# aparture_v1.net
KiCad netlist of a schematic drawn in EAGLE
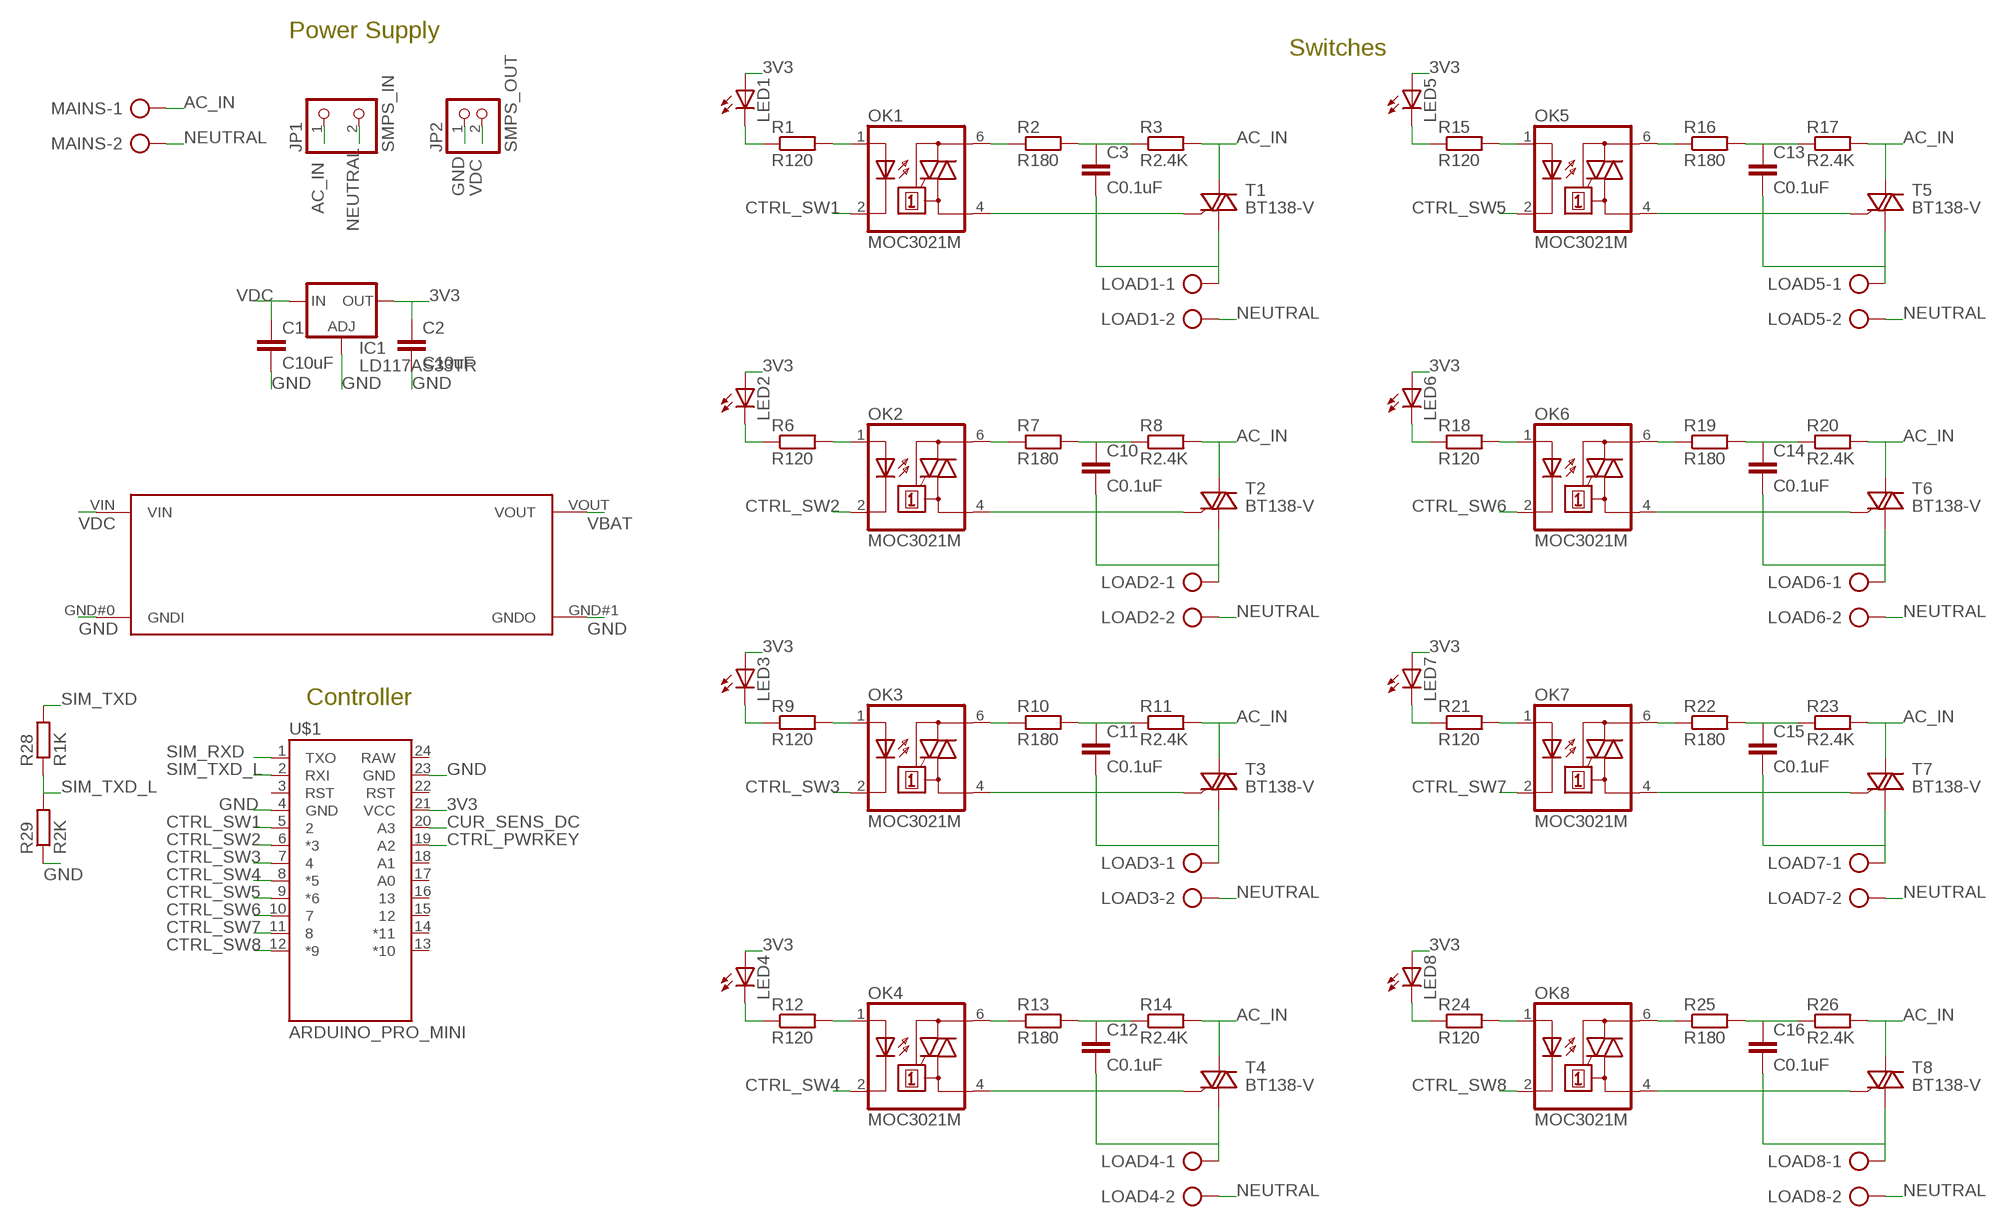
[diagram p0: schematic, sheet 1, part 1 of 2]
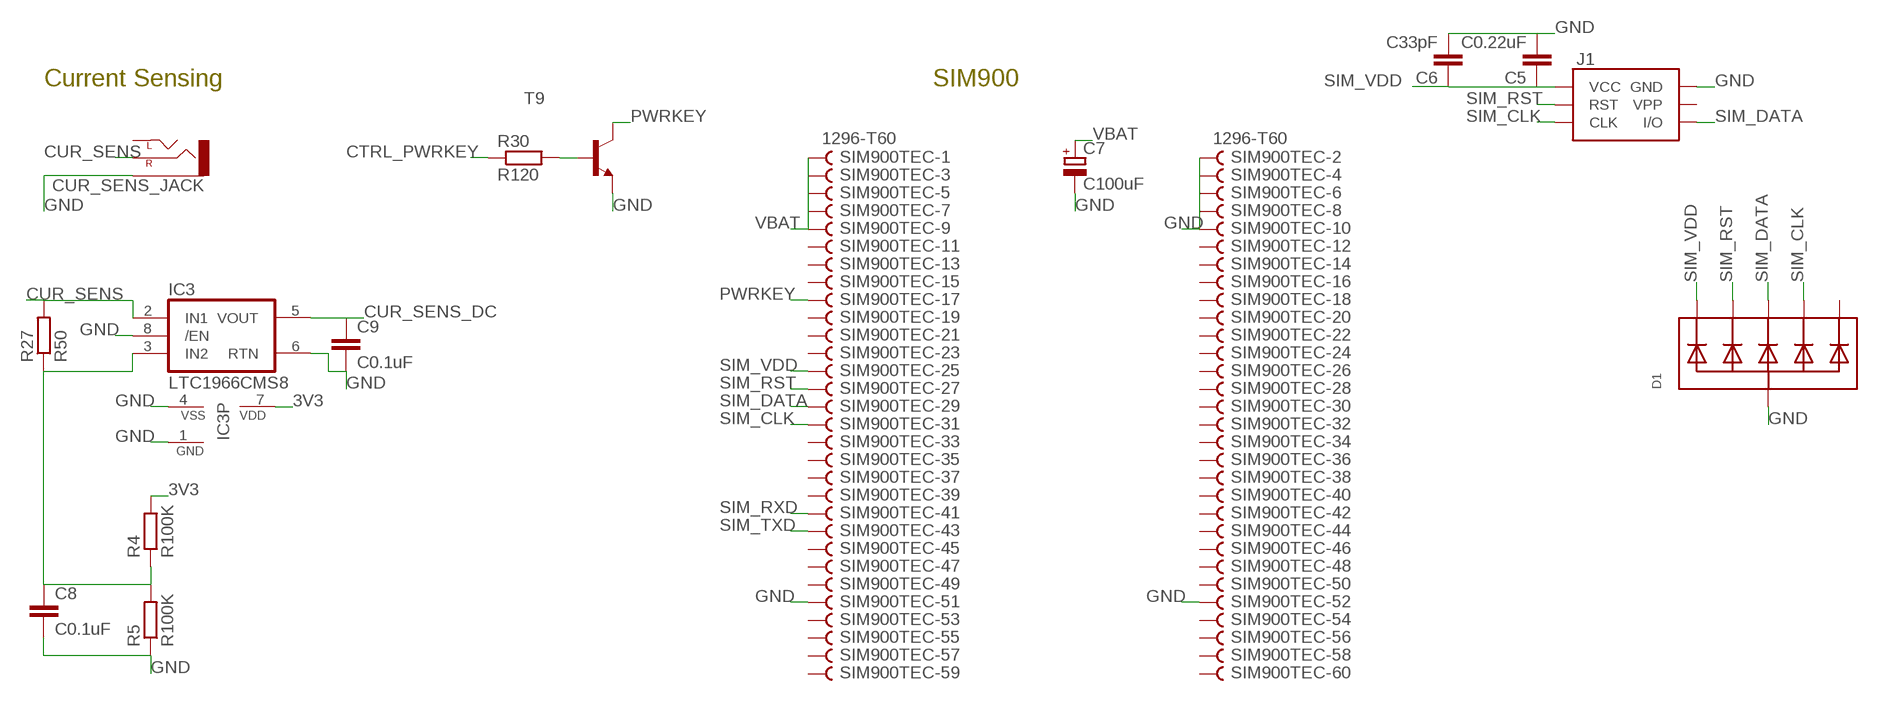
[diagram p1: schematic, sheet 1, part 2 of 2]

(export (version "E")
  (design (tool "Eeschema 10.0.6"))
  (components
    (comp (ref "C1")
      (value "C10uF")
      (footprint "eagle-import:C0805")
      (libsource (lib "eagle-import") (part "C-EUC0805"))
    )
    (comp (ref "C2")
      (value "C10uF")
      (footprint "eagle-import:C0805")
      (libsource (lib "eagle-import") (part "C-EUC0805"))
    )
    (comp (ref "C3")
      (value "C0.1uF")
      (footprint "eagle-import:C0805")
      (libsource (lib "eagle-import") (part "C-EUC0805"))
    )
    (comp (ref "C5")
      (value "C0.22uF")
      (footprint "eagle-import:C0805")
      (libsource (lib "eagle-import") (part "C-EUC0805"))
    )
    (comp (ref "C6")
      (value "C33pF")
      (footprint "eagle-import:C0805")
      (libsource (lib "eagle-import") (part "C-EUC0805"))
    )
    (comp (ref "C7")
      (value "C100uF")
      (footprint "eagle-import:153CLV-0605")
      (libsource (lib "eagle-import") (part "CPOL-EU153CLV-0605"))
    )
    (comp (ref "C8")
      (value "C0.1uF")
      (footprint "eagle-import:C0805")
      (libsource (lib "eagle-import") (part "C-EUC0805"))
    )
    (comp (ref "C9")
      (value "C0.1uF")
      (footprint "eagle-import:C0805")
      (libsource (lib "eagle-import") (part "C-EUC0805"))
    )
    (comp (ref "C10")
      (value "C0.1uF")
      (footprint "eagle-import:C0805")
      (libsource (lib "eagle-import") (part "C-EUC0805"))
    )
    (comp (ref "C11")
      (value "C0.1uF")
      (footprint "eagle-import:C0805")
      (libsource (lib "eagle-import") (part "C-EUC0805"))
    )
    (comp (ref "C12")
      (value "C0.1uF")
      (footprint "eagle-import:C0805")
      (libsource (lib "eagle-import") (part "C-EUC0805"))
    )
    (comp (ref "C13")
      (value "C0.1uF")
      (footprint "eagle-import:C0805")
      (libsource (lib "eagle-import") (part "C-EUC0805"))
    )
    (comp (ref "C14")
      (value "C0.1uF")
      (footprint "eagle-import:C0805")
      (libsource (lib "eagle-import") (part "C-EUC0805"))
    )
    (comp (ref "C15")
      (value "C0.1uF")
      (footprint "eagle-import:C0805")
      (libsource (lib "eagle-import") (part "C-EUC0805"))
    )
    (comp (ref "C16")
      (value "C0.1uF")
      (footprint "eagle-import:C0805")
      (libsource (lib "eagle-import") (part "C-EUC0805"))
    )
    (comp (ref "CUR_SENS_JACK")
      (value "AUDIO-JACKSMD2")
      (footprint "eagle-import:AUDIO-JACK-3.5MM-SMD")
      (libsource (lib "eagle-import") (part "AUDIO-JACKSMD2"))
    )
    (comp (ref "D1")
      (value "TVSARRAY_5LANE")
      (footprint "eagle-import:SOT363")
      (libsource (lib "eagle-import") (part "TVSARRAY_5LANE"))
    )
    (comp (ref "IC1")
      (value "LD117AS33TR")
      (footprint "eagle-import:SOT223")
      (libsource (lib "eagle-import") (part "LD117A?S33TR"))
    )
    (comp (ref "IC3")
      (value "LTC1966CMS8")
      (footprint "eagle-import:MSOP8")
      (libsource (lib "eagle-import") (part "LTC1966MS8C"))
    )
    (comp (ref "J1")
      (value "SIMHOLDERSIM")
      (footprint "eagle-import:SIMHOLDER")
      (libsource (lib "eagle-import") (part "SIMHOLDERSIM"))
    )
    (comp (ref "JP1")
      (value "SMPS_IN")
      (footprint "eagle-import:SMPS_IN")
      (libsource (lib "eagle-import") (part "SMPS_IN"))
    )
    (comp (ref "JP2")
      (value "SMPS_OUT")
      (footprint "eagle-import:1X02")
      (libsource (lib "eagle-import") (part "PINHD-1X2"))
    )
    (comp (ref "LED1")
      (value "LED3MM")
      (footprint "eagle-import:LED3MM")
      (libsource (lib "eagle-import") (part "LED3MM"))
    )
    (comp (ref "LED2")
      (value "LED3MM")
      (footprint "eagle-import:LED3MM")
      (libsource (lib "eagle-import") (part "LED3MM"))
    )
    (comp (ref "LED3")
      (value "LED3MM")
      (footprint "eagle-import:LED3MM")
      (libsource (lib "eagle-import") (part "LED3MM"))
    )
    (comp (ref "LED4")
      (value "LED3MM")
      (footprint "eagle-import:LED3MM")
      (libsource (lib "eagle-import") (part "LED3MM"))
    )
    (comp (ref "LED5")
      (value "LED3MM")
      (footprint "eagle-import:LED3MM")
      (libsource (lib "eagle-import") (part "LED3MM"))
    )
    (comp (ref "LED6")
      (value "LED3MM")
      (footprint "eagle-import:LED3MM")
      (libsource (lib "eagle-import") (part "LED3MM"))
    )
    (comp (ref "LED7")
      (value "LED3MM")
      (footprint "eagle-import:LED3MM")
      (libsource (lib "eagle-import") (part "LED3MM"))
    )
    (comp (ref "LED8")
      (value "LED3MM")
      (footprint "eagle-import:LED3MM")
      (libsource (lib "eagle-import") (part "LED3MM"))
    )
    (comp (ref "LOAD1")
      (value "AK300/2")
      (footprint "eagle-import:AK300_2")
      (fields (field (name "OC_FARNELL") "unknown") (field (name "OC_NEWARK") "unknown"))
      (libsource (lib "eagle-import") (part "AK300/2"))
    )
    (comp (ref "LOAD2")
      (value "AK300/2")
      (footprint "eagle-import:AK300_2")
      (fields (field (name "OC_FARNELL") "unknown") (field (name "OC_NEWARK") "unknown"))
      (libsource (lib "eagle-import") (part "AK300/2"))
    )
    (comp (ref "LOAD3")
      (value "AK300/2")
      (footprint "eagle-import:AK300_2")
      (fields (field (name "OC_FARNELL") "unknown") (field (name "OC_NEWARK") "unknown"))
      (libsource (lib "eagle-import") (part "AK300/2"))
    )
    (comp (ref "LOAD4")
      (value "AK300/2")
      (footprint "eagle-import:AK300_2")
      (fields (field (name "OC_FARNELL") "unknown") (field (name "OC_NEWARK") "unknown"))
      (libsource (lib "eagle-import") (part "AK300/2"))
    )
    (comp (ref "LOAD5")
      (value "AK300/2")
      (footprint "eagle-import:AK300_2")
      (fields (field (name "OC_FARNELL") "unknown") (field (name "OC_NEWARK") "unknown"))
      (libsource (lib "eagle-import") (part "AK300/2"))
    )
    (comp (ref "LOAD6")
      (value "AK300/2")
      (footprint "eagle-import:AK300_2")
      (fields (field (name "OC_FARNELL") "unknown") (field (name "OC_NEWARK") "unknown"))
      (libsource (lib "eagle-import") (part "AK300/2"))
    )
    (comp (ref "LOAD7")
      (value "AK300/2")
      (footprint "eagle-import:AK300_2")
      (fields (field (name "OC_FARNELL") "unknown") (field (name "OC_NEWARK") "unknown"))
      (libsource (lib "eagle-import") (part "AK300/2"))
    )
    (comp (ref "LOAD8")
      (value "AK300/2")
      (footprint "eagle-import:AK300_2")
      (fields (field (name "OC_FARNELL") "unknown") (field (name "OC_NEWARK") "unknown"))
      (libsource (lib "eagle-import") (part "AK300/2"))
    )
    (comp (ref "MAINS")
      (value "AK300/2")
      (footprint "eagle-import:AK300_2")
      (libsource (lib "eagle-import") (part "AK300/2"))
    )
    (comp (ref "OK1")
      (value "MOC3021M")
      (footprint "eagle-import:DIL06")
      (fields (field (name "MF") "FAIRCHILD SEMICONDUCTOR") (field (name "MPN") "MOC3021-M"))
      (libsource (lib "eagle-import") (part "MOC30M21"))
    )
    (comp (ref "OK2")
      (value "MOC3021M")
      (footprint "eagle-import:DIL06")
      (fields (field (name "MF") "FAIRCHILD SEMICONDUCTOR") (field (name "MPN") "MOC3021-M"))
      (libsource (lib "eagle-import") (part "MOC30M21"))
    )
    (comp (ref "OK3")
      (value "MOC3021M")
      (footprint "eagle-import:DIL06")
      (fields (field (name "MF") "FAIRCHILD SEMICONDUCTOR") (field (name "MPN") "MOC3021-M"))
      (libsource (lib "eagle-import") (part "MOC30M21"))
    )
    (comp (ref "OK4")
      (value "MOC3021M")
      (footprint "eagle-import:DIL06")
      (fields (field (name "MF") "FAIRCHILD SEMICONDUCTOR") (field (name "MPN") "MOC3021-M"))
      (libsource (lib "eagle-import") (part "MOC30M21"))
    )
    (comp (ref "OK5")
      (value "MOC3021M")
      (footprint "eagle-import:DIL06")
      (fields (field (name "MF") "FAIRCHILD SEMICONDUCTOR") (field (name "MPN") "MOC3021-M"))
      (libsource (lib "eagle-import") (part "MOC30M21"))
    )
    (comp (ref "OK6")
      (value "MOC3021M")
      (footprint "eagle-import:DIL06")
      (fields (field (name "MF") "FAIRCHILD SEMICONDUCTOR") (field (name "MPN") "MOC3021-M"))
      (libsource (lib "eagle-import") (part "MOC30M21"))
    )
    (comp (ref "OK7")
      (value "MOC3021M")
      (footprint "eagle-import:DIL06")
      (fields (field (name "MF") "FAIRCHILD SEMICONDUCTOR") (field (name "MPN") "MOC3021-M"))
      (libsource (lib "eagle-import") (part "MOC30M21"))
    )
    (comp (ref "OK8")
      (value "MOC3021M")
      (footprint "eagle-import:DIL06")
      (fields (field (name "MF") "FAIRCHILD SEMICONDUCTOR") (field (name "MPN") "MOC3021-M"))
      (libsource (lib "eagle-import") (part "MOC30M21"))
    )
    (comp (ref "R1")
      (value "R120")
      (footprint "eagle-import:M0805")
      (libsource (lib "eagle-import") (part "R-EU_M0805"))
    )
    (comp (ref "R2")
      (value "R180")
      (footprint "eagle-import:M0805")
      (libsource (lib "eagle-import") (part "R-EU_M0805"))
    )
    (comp (ref "R3")
      (value "R2.4K")
      (footprint "eagle-import:M0805")
      (libsource (lib "eagle-import") (part "R-EU_M0805"))
    )
    (comp (ref "R4")
      (value "R100K")
      (footprint "eagle-import:M0805")
      (libsource (lib "eagle-import") (part "R-EU_M0805"))
    )
    (comp (ref "R5")
      (value "R100K")
      (footprint "eagle-import:M0805")
      (libsource (lib "eagle-import") (part "R-EU_M0805"))
    )
    (comp (ref "R6")
      (value "R120")
      (footprint "eagle-import:M0805")
      (libsource (lib "eagle-import") (part "R-EU_M0805"))
    )
    (comp (ref "R7")
      (value "R180")
      (footprint "eagle-import:M0805")
      (libsource (lib "eagle-import") (part "R-EU_M0805"))
    )
    (comp (ref "R8")
      (value "R2.4K")
      (footprint "eagle-import:M0805")
      (libsource (lib "eagle-import") (part "R-EU_M0805"))
    )
    (comp (ref "R9")
      (value "R120")
      (footprint "eagle-import:M0805")
      (libsource (lib "eagle-import") (part "R-EU_M0805"))
    )
    (comp (ref "R10")
      (value "R180")
      (footprint "eagle-import:M0805")
      (libsource (lib "eagle-import") (part "R-EU_M0805"))
    )
    (comp (ref "R11")
      (value "R2.4K")
      (footprint "eagle-import:M0805")
      (libsource (lib "eagle-import") (part "R-EU_M0805"))
    )
    (comp (ref "R12")
      (value "R120")
      (footprint "eagle-import:M0805")
      (libsource (lib "eagle-import") (part "R-EU_M0805"))
    )
    (comp (ref "R13")
      (value "R180")
      (footprint "eagle-import:M0805")
      (libsource (lib "eagle-import") (part "R-EU_M0805"))
    )
    (comp (ref "R14")
      (value "R2.4K")
      (footprint "eagle-import:M0805")
      (libsource (lib "eagle-import") (part "R-EU_M0805"))
    )
    (comp (ref "R15")
      (value "R120")
      (footprint "eagle-import:M0805")
      (libsource (lib "eagle-import") (part "R-EU_M0805"))
    )
    (comp (ref "R16")
      (value "R180")
      (footprint "eagle-import:M0805")
      (libsource (lib "eagle-import") (part "R-EU_M0805"))
    )
    (comp (ref "R17")
      (value "R2.4K")
      (footprint "eagle-import:M0805")
      (libsource (lib "eagle-import") (part "R-EU_M0805"))
    )
    (comp (ref "R18")
      (value "R120")
      (footprint "eagle-import:M0805")
      (libsource (lib "eagle-import") (part "R-EU_M0805"))
    )
    (comp (ref "R19")
      (value "R180")
      (footprint "eagle-import:M0805")
      (libsource (lib "eagle-import") (part "R-EU_M0805"))
    )
    (comp (ref "R20")
      (value "R2.4K")
      (footprint "eagle-import:M0805")
      (libsource (lib "eagle-import") (part "R-EU_M0805"))
    )
    (comp (ref "R21")
      (value "R120")
      (footprint "eagle-import:M0805")
      (libsource (lib "eagle-import") (part "R-EU_M0805"))
    )
    (comp (ref "R22")
      (value "R180")
      (footprint "eagle-import:M0805")
      (libsource (lib "eagle-import") (part "R-EU_M0805"))
    )
    (comp (ref "R23")
      (value "R2.4K")
      (footprint "eagle-import:M0805")
      (libsource (lib "eagle-import") (part "R-EU_M0805"))
    )
    (comp (ref "R24")
      (value "R120")
      (footprint "eagle-import:M0805")
      (libsource (lib "eagle-import") (part "R-EU_M0805"))
    )
    (comp (ref "R25")
      (value "R180")
      (footprint "eagle-import:M0805")
      (libsource (lib "eagle-import") (part "R-EU_M0805"))
    )
    (comp (ref "R26")
      (value "R2.4K")
      (footprint "eagle-import:M0805")
      (libsource (lib "eagle-import") (part "R-EU_M0805"))
    )
    (comp (ref "R27")
      (value "R50")
      (footprint "eagle-import:M0805")
      (libsource (lib "eagle-import") (part "R-EU_M0805"))
    )
    (comp (ref "R28")
      (value "R1K")
      (footprint "eagle-import:M0805")
      (libsource (lib "eagle-import") (part "R-EU_M0805"))
    )
    (comp (ref "R29")
      (value "R2K")
      (footprint "eagle-import:M0805")
      (libsource (lib "eagle-import") (part "R-EU_M0805"))
    )
    (comp (ref "R30")
      (value "R120")
      (footprint "eagle-import:M0805")
      (libsource (lib "eagle-import") (part "R-EU_M0805"))
    )
    (comp (ref "SIM900TEC")
      (value "1296-T60")
      (footprint "eagle-import:1296-60")
      (libsource (lib "eagle-import") (part "1296-T60"))
    )
    (comp (ref "T1")
      (value "BT138-V")
      (footprint "eagle-import:TO220BV")
      (libsource (lib "eagle-import") (part "BT138-V"))
    )
    (comp (ref "T2")
      (value "BT138-V")
      (footprint "eagle-import:TO220BV")
      (libsource (lib "eagle-import") (part "BT138-V"))
    )
    (comp (ref "T3")
      (value "BT138-V")
      (footprint "eagle-import:TO220BV")
      (libsource (lib "eagle-import") (part "BT138-V"))
    )
    (comp (ref "T4")
      (value "BT138-V")
      (footprint "eagle-import:TO220BV")
      (libsource (lib "eagle-import") (part "BT138-V"))
    )
    (comp (ref "T5")
      (value "BT138-V")
      (footprint "eagle-import:TO220BV")
      (libsource (lib "eagle-import") (part "BT138-V"))
    )
    (comp (ref "T6")
      (value "BT138-V")
      (footprint "eagle-import:TO220BV")
      (libsource (lib "eagle-import") (part "BT138-V"))
    )
    (comp (ref "T7")
      (value "BT138-V")
      (footprint "eagle-import:TO220BV")
      (libsource (lib "eagle-import") (part "BT138-V"))
    )
    (comp (ref "T8")
      (value "BT138-V")
      (footprint "eagle-import:TO220BV")
      (libsource (lib "eagle-import") (part "BT138-V"))
    )
    (comp (ref "T9")
      (value "MMBT2222ALT1-NPN-SOT23-BEC")
      (footprint "eagle-import:SOT23-BEC")
      (libsource (lib "eagle-import") (part "-NPN-SOT23-BECMMBT2222ALT1"))
    )
    (comp (ref "U$1")
      (value "ARDUINO_PRO_MINI")
      (footprint "eagle-import:ARDUINO_PRO_MINI")
      (libsource (lib "eagle-import") (part "ARDUINO_PRO_MINI"))
    )
    (comp (ref "VOL_REG_SIM900")
      (value "DCDCMODULE")
      (footprint "eagle-import:DCDCMODULE")
      (libsource (lib "eagle-import") (part "DCDCMODULE"))
    )
  )
  (nets
    (net (code "1") (name "/3V3") (class "Default")
      (node (ref "C2") (pin "1") (pinfunction "1_1") (pintype "passive"))
      (node (ref "IC1") (pin "4") (pinfunction "OUT_4") (pintype "passive"))
      (node (ref "IC3") (pin "7") (pinfunction "VDD_7") (pintype "power_in"))
      (node (ref "LED1") (pin "A") (pinfunction "A_A") (pintype "passive"))
      (node (ref "LED2") (pin "A") (pinfunction "A_A") (pintype "passive"))
      (node (ref "LED3") (pin "A") (pinfunction "A_A") (pintype "passive"))
      (node (ref "LED4") (pin "A") (pinfunction "A_A") (pintype "passive"))
      (node (ref "LED5") (pin "A") (pinfunction "A_A") (pintype "passive"))
      (node (ref "LED6") (pin "A") (pinfunction "A_A") (pintype "passive"))
      (node (ref "LED7") (pin "A") (pinfunction "A_A") (pintype "passive"))
      (node (ref "LED8") (pin "A") (pinfunction "A_A") (pintype "passive"))
      (node (ref "R4") (pin "2") (pinfunction "2_2") (pintype "passive"))
      (node (ref "U$1") (pin "21") (pinfunction "VCC_21") (pintype "bidirectional"))
    )
    (net (code "2") (name "/AC_IN") (class "Default")
      (node (ref "JP1") (pin "1") (pinfunction "1_1") (pintype "passive"))
      (node (ref "MAINS") (pin "1") (pinfunction "KL_1") (pintype "passive"))
      (node (ref "R11") (pin "2") (pinfunction "2_2") (pintype "passive"))
      (node (ref "R14") (pin "2") (pinfunction "2_2") (pintype "passive"))
      (node (ref "R17") (pin "2") (pinfunction "2_2") (pintype "passive"))
      (node (ref "R20") (pin "2") (pinfunction "2_2") (pintype "passive"))
      (node (ref "R23") (pin "2") (pinfunction "2_2") (pintype "passive"))
      (node (ref "R26") (pin "2") (pinfunction "2_2") (pintype "passive"))
      (node (ref "R3") (pin "2") (pinfunction "2_2") (pintype "passive"))
      (node (ref "R8") (pin "2") (pinfunction "2_2") (pintype "passive"))
      (node (ref "T1") (pin "T2") (pinfunction "A2_T2") (pintype "passive"))
      (node (ref "T2") (pin "T2") (pinfunction "A2_T2") (pintype "passive"))
      (node (ref "T3") (pin "T2") (pinfunction "A2_T2") (pintype "passive"))
      (node (ref "T4") (pin "T2") (pinfunction "A2_T2") (pintype "passive"))
      (node (ref "T5") (pin "T2") (pinfunction "A2_T2") (pintype "passive"))
      (node (ref "T6") (pin "T2") (pinfunction "A2_T2") (pintype "passive"))
      (node (ref "T7") (pin "T2") (pinfunction "A2_T2") (pintype "passive"))
      (node (ref "T8") (pin "T2") (pinfunction "A2_T2") (pintype "passive"))
    )
    (net (code "3") (name "/CTRL_PWRKEY") (class "Default")
      (node (ref "R30") (pin "1") (pinfunction "1_1") (pintype "passive"))
      (node (ref "U$1") (pin "19") (pinfunction "A2_19") (pintype "bidirectional"))
    )
    (net (code "4") (name "/CTRL_SW1") (class "Default")
      (node (ref "OK1") (pin "2") (pinfunction "C_2") (pintype "passive"))
      (node (ref "U$1") (pin "5") (pinfunction "2_5") (pintype "bidirectional"))
    )
    (net (code "5") (name "/CTRL_SW2") (class "Default")
      (node (ref "OK2") (pin "2") (pinfunction "C_2") (pintype "passive"))
      (node (ref "U$1") (pin "6") (pinfunction "*3_6") (pintype "bidirectional"))
    )
    (net (code "6") (name "/CTRL_SW3") (class "Default")
      (node (ref "OK3") (pin "2") (pinfunction "C_2") (pintype "passive"))
      (node (ref "U$1") (pin "7") (pinfunction "4_7") (pintype "bidirectional"))
    )
    (net (code "7") (name "/CTRL_SW4") (class "Default")
      (node (ref "OK4") (pin "2") (pinfunction "C_2") (pintype "passive"))
      (node (ref "U$1") (pin "8") (pinfunction "*5_8") (pintype "bidirectional"))
    )
    (net (code "8") (name "/CTRL_SW5") (class "Default")
      (node (ref "OK5") (pin "2") (pinfunction "C_2") (pintype "passive"))
      (node (ref "U$1") (pin "9") (pinfunction "*6_9") (pintype "bidirectional"))
    )
    (net (code "9") (name "/CTRL_SW6") (class "Default")
      (node (ref "OK6") (pin "2") (pinfunction "C_2") (pintype "passive"))
      (node (ref "U$1") (pin "10") (pinfunction "7_10") (pintype "bidirectional"))
    )
    (net (code "10") (name "/CTRL_SW7") (class "Default")
      (node (ref "OK7") (pin "2") (pinfunction "C_2") (pintype "passive"))
      (node (ref "U$1") (pin "11") (pinfunction "8_11") (pintype "bidirectional"))
    )
    (net (code "11") (name "/CTRL_SW8") (class "Default")
      (node (ref "OK8") (pin "2") (pinfunction "C_2") (pintype "passive"))
      (node (ref "U$1") (pin "12") (pinfunction "*9_12") (pintype "bidirectional"))
    )
    (net (code "12") (name "/CUR_SENS") (class "Default")
      (node (ref "CUR_SENS_JACK") (pin "RING") (pinfunction "RIGHT_RING") (pintype "bidirectional"))
      (node (ref "IC3") (pin "2") (pinfunction "IN1_2") (pintype "input"))
      (node (ref "R27") (pin "2") (pinfunction "2_2") (pintype "passive"))
    )
    (net (code "13") (name "/CUR_SENS_DC") (class "Default")
      (node (ref "C9") (pin "1") (pinfunction "1_1") (pintype "passive"))
      (node (ref "IC3") (pin "5") (pinfunction "VOUT_5") (pintype "output"))
      (node (ref "U$1") (pin "20") (pinfunction "A3_20") (pintype "bidirectional"))
    )
    (net (code "14") (name "/GND") (class "Default")
      (node (ref "C1") (pin "2") (pinfunction "2_2") (pintype "passive"))
      (node (ref "C2") (pin "2") (pinfunction "2_2") (pintype "passive"))
      (node (ref "C5") (pin "2") (pinfunction "2_2") (pintype "passive"))
      (node (ref "C6") (pin "2") (pinfunction "2_2") (pintype "passive"))
      (node (ref "C7") (pin "-") (pinfunction "-_-") (pintype "passive"))
      (node (ref "C8") (pin "2") (pinfunction "2_2") (pintype "passive"))
      (node (ref "C9") (pin "2") (pinfunction "2_2") (pintype "passive"))
      (node (ref "CUR_SENS_JACK") (pin "SLEEVE") (pinfunction "SLEEVE_SLEEVE") (pintype "bidirectional"))
      (node (ref "D1") (pin "2") (pinfunction "A_2") (pintype "passive"))
      (node (ref "IC1") (pin "1") (pinfunction "ADJ_1") (pintype "input"))
      (node (ref "IC3") (pin "1") (pinfunction "GND_1") (pintype "power_in"))
      (node (ref "IC3") (pin "4") (pinfunction "VSS_4") (pintype "power_in"))
      (node (ref "IC3") (pin "6") (pinfunction "RTN_6") (pintype "passive"))
      (node (ref "IC3") (pin "8") (pinfunction "/EN_8") (pintype "input"))
      (node (ref "J1") (pin "C5") (pinfunction "GND_C5") (pintype "power_in"))
      (node (ref "JP2") (pin "1") (pinfunction "1_1") (pintype "passive"))
      (node (ref "R29") (pin "1") (pinfunction "1_1") (pintype "passive"))
      (node (ref "R5") (pin "1") (pinfunction "1_1") (pintype "passive"))
      (node (ref "SIM900TEC") (pin "10") (pinfunction "B_10") (pintype "passive"))
      (node (ref "SIM900TEC") (pin "2") (pinfunction "B_2") (pintype "passive"))
      (node (ref "SIM900TEC") (pin "4") (pinfunction "B_4") (pintype "passive"))
      (node (ref "SIM900TEC") (pin "51") (pinfunction "B_51") (pintype "passive"))
      (node (ref "SIM900TEC") (pin "52") (pinfunction "B_52") (pintype "passive"))
      (node (ref "SIM900TEC") (pin "6") (pinfunction "B_6") (pintype "passive"))
      (node (ref "SIM900TEC") (pin "8") (pinfunction "B_8") (pintype "passive"))
      (node (ref "T9") (pin "E") (pinfunction "E_E") (pintype "passive"))
      (node (ref "U$1") (pin "23") (pinfunction "GND_23") (pintype "bidirectional"))
      (node (ref "U$1") (pin "4") (pinfunction "GND_4") (pintype "bidirectional"))
      (node (ref "VOL_REG_SIM900") (pin "GND#0") (pinfunction "GNDI_GND#0") (pintype "bidirectional"))
      (node (ref "VOL_REG_SIM900") (pin "GND#1") (pinfunction "GNDO_GND#1") (pintype "bidirectional"))
    )
    (net (code "15") (name "/NEUTRAL") (class "Default")
      (node (ref "JP1") (pin "2") (pinfunction "2_2") (pintype "passive"))
      (node (ref "LOAD1") (pin "2") (pinfunction "KL_2") (pintype "passive"))
      (node (ref "LOAD2") (pin "2") (pinfunction "KL_2") (pintype "passive"))
      (node (ref "LOAD3") (pin "2") (pinfunction "KL_2") (pintype "passive"))
      (node (ref "LOAD4") (pin "2") (pinfunction "KL_2") (pintype "passive"))
      (node (ref "LOAD5") (pin "2") (pinfunction "KL_2") (pintype "passive"))
      (node (ref "LOAD6") (pin "2") (pinfunction "KL_2") (pintype "passive"))
      (node (ref "LOAD7") (pin "2") (pinfunction "KL_2") (pintype "passive"))
      (node (ref "LOAD8") (pin "2") (pinfunction "KL_2") (pintype "passive"))
      (node (ref "MAINS") (pin "2") (pinfunction "KL_2") (pintype "passive"))
    )
    (net (code "16") (name "/PWRKEY") (class "Default")
      (node (ref "SIM900TEC") (pin "17") (pinfunction "B_17") (pintype "passive"))
      (node (ref "T9") (pin "C") (pinfunction "C_C") (pintype "passive"))
    )
    (net (code "17") (name "/SIM_CLK") (class "Default")
      (node (ref "D1") (pin "5") (pinfunction "C4_5") (pintype "passive"))
      (node (ref "J1") (pin "C3") (pinfunction "CLK_C3") (pintype "input"))
      (node (ref "SIM900TEC") (pin "31") (pinfunction "B_31") (pintype "passive"))
    )
    (net (code "18") (name "/SIM_DATA") (class "Default")
      (node (ref "D1") (pin "4") (pinfunction "C3_4") (pintype "passive"))
      (node (ref "J1") (pin "C7") (pinfunction "I/O_C7") (pintype "bidirectional"))
      (node (ref "SIM900TEC") (pin "29") (pinfunction "B_29") (pintype "passive"))
    )
    (net (code "19") (name "/SIM_RST") (class "Default")
      (node (ref "D1") (pin "3") (pinfunction "C2_3") (pintype "passive"))
      (node (ref "J1") (pin "C2") (pinfunction "RST_C2") (pintype "input"))
      (node (ref "SIM900TEC") (pin "27") (pinfunction "B_27") (pintype "passive"))
    )
    (net (code "20") (name "/SIM_RXD") (class "Default")
      (node (ref "SIM900TEC") (pin "41") (pinfunction "B_41") (pintype "passive"))
      (node (ref "U$1") (pin "1") (pinfunction "TXO_1") (pintype "bidirectional"))
    )
    (net (code "21") (name "/SIM_TXD") (class "Default")
      (node (ref "R28") (pin "2") (pinfunction "2_2") (pintype "passive"))
      (node (ref "SIM900TEC") (pin "43") (pinfunction "B_43") (pintype "passive"))
    )
    (net (code "22") (name "/SIM_TXD_L") (class "Default")
      (node (ref "R28") (pin "1") (pinfunction "1_1") (pintype "passive"))
      (node (ref "R29") (pin "2") (pinfunction "2_2") (pintype "passive"))
      (node (ref "U$1") (pin "2") (pinfunction "RXI_2") (pintype "bidirectional"))
    )
    (net (code "23") (name "/SIM_VDD") (class "Default")
      (node (ref "C5") (pin "1") (pinfunction "1_1") (pintype "passive"))
      (node (ref "C6") (pin "1") (pinfunction "1_1") (pintype "passive"))
      (node (ref "D1") (pin "1") (pinfunction "C1_1") (pintype "passive"))
      (node (ref "J1") (pin "C1") (pinfunction "VCC_C1") (pintype "power_in"))
      (node (ref "SIM900TEC") (pin "25") (pinfunction "B_25") (pintype "passive"))
    )
    (net (code "24") (name "/VBAT") (class "Default")
      (node (ref "C7") (pin "+") (pinfunction "+_+") (pintype "passive"))
      (node (ref "SIM900TEC") (pin "1") (pinfunction "B_1") (pintype "passive"))
      (node (ref "SIM900TEC") (pin "3") (pinfunction "B_3") (pintype "passive"))
      (node (ref "SIM900TEC") (pin "5") (pinfunction "B_5") (pintype "passive"))
      (node (ref "SIM900TEC") (pin "7") (pinfunction "B_7") (pintype "passive"))
      (node (ref "SIM900TEC") (pin "9") (pinfunction "B_9") (pintype "passive"))
      (node (ref "VOL_REG_SIM900") (pin "VOUT") (pinfunction "VOUT_VOUT") (pintype "bidirectional"))
    )
    (net (code "25") (name "/VDC") (class "Default")
      (node (ref "C1") (pin "1") (pinfunction "1_1") (pintype "passive"))
      (node (ref "IC1") (pin "3") (pinfunction "IN_3") (pintype "input"))
      (node (ref "JP2") (pin "2") (pinfunction "2_2") (pintype "passive"))
      (node (ref "VOL_REG_SIM900") (pin "VIN") (pinfunction "VIN_VIN") (pintype "bidirectional"))
    )
    (net (code "26") (name "Net-(C3-Pad1)") (class "Default")
      (node (ref "C3") (pin "1") (pinfunction "1_1") (pintype "passive"))
      (node (ref "R2") (pin "2") (pinfunction "2_2") (pintype "passive"))
      (node (ref "R3") (pin "1") (pinfunction "1_1") (pintype "passive"))
    )
    (net (code "27") (name "Net-(C10-Pad1)") (class "Default")
      (node (ref "C10") (pin "1") (pinfunction "1_1") (pintype "passive"))
      (node (ref "R7") (pin "2") (pinfunction "2_2") (pintype "passive"))
      (node (ref "R8") (pin "1") (pinfunction "1_1") (pintype "passive"))
    )
    (net (code "28") (name "Net-(C11-Pad1)") (class "Default")
      (node (ref "C11") (pin "1") (pinfunction "1_1") (pintype "passive"))
      (node (ref "R10") (pin "2") (pinfunction "2_2") (pintype "passive"))
      (node (ref "R11") (pin "1") (pinfunction "1_1") (pintype "passive"))
    )
    (net (code "29") (name "Net-(C12-Pad1)") (class "Default")
      (node (ref "C12") (pin "1") (pinfunction "1_1") (pintype "passive"))
      (node (ref "R13") (pin "2") (pinfunction "2_2") (pintype "passive"))
      (node (ref "R14") (pin "1") (pinfunction "1_1") (pintype "passive"))
    )
    (net (code "30") (name "Net-(C13-Pad1)") (class "Default")
      (node (ref "C13") (pin "1") (pinfunction "1_1") (pintype "passive"))
      (node (ref "R16") (pin "2") (pinfunction "2_2") (pintype "passive"))
      (node (ref "R17") (pin "1") (pinfunction "1_1") (pintype "passive"))
    )
    (net (code "31") (name "Net-(C14-Pad1)") (class "Default")
      (node (ref "C14") (pin "1") (pinfunction "1_1") (pintype "passive"))
      (node (ref "R19") (pin "2") (pinfunction "2_2") (pintype "passive"))
      (node (ref "R20") (pin "1") (pinfunction "1_1") (pintype "passive"))
    )
    (net (code "32") (name "Net-(C15-Pad1)") (class "Default")
      (node (ref "C15") (pin "1") (pinfunction "1_1") (pintype "passive"))
      (node (ref "R22") (pin "2") (pinfunction "2_2") (pintype "passive"))
      (node (ref "R23") (pin "1") (pinfunction "1_1") (pintype "passive"))
    )
    (net (code "33") (name "Net-(C16-Pad1)") (class "Default")
      (node (ref "C16") (pin "1") (pinfunction "1_1") (pintype "passive"))
      (node (ref "R25") (pin "2") (pinfunction "2_2") (pintype "passive"))
      (node (ref "R26") (pin "1") (pinfunction "1_1") (pintype "passive"))
    )
    (net (code "34") (name "Net-(IC3A-IN2)") (class "Default")
      (node (ref "C8") (pin "1") (pinfunction "1_1") (pintype "passive"))
      (node (ref "IC3") (pin "3") (pinfunction "IN2_3") (pintype "input"))
      (node (ref "R27") (pin "1") (pinfunction "1_1") (pintype "passive"))
      (node (ref "R4") (pin "1") (pinfunction "1_1") (pintype "passive"))
      (node (ref "R5") (pin "2") (pinfunction "2_2") (pintype "passive"))
    )
    (net (code "35") (name "Net-(LED1-C)") (class "Default")
      (node (ref "LED1") (pin "K") (pinfunction "C_K") (pintype "passive"))
      (node (ref "R1") (pin "1") (pinfunction "1_1") (pintype "passive"))
    )
    (net (code "36") (name "Net-(LED2-C)") (class "Default")
      (node (ref "LED2") (pin "K") (pinfunction "C_K") (pintype "passive"))
      (node (ref "R6") (pin "1") (pinfunction "1_1") (pintype "passive"))
    )
    (net (code "37") (name "Net-(LED3-C)") (class "Default")
      (node (ref "LED3") (pin "K") (pinfunction "C_K") (pintype "passive"))
      (node (ref "R9") (pin "1") (pinfunction "1_1") (pintype "passive"))
    )
    (net (code "38") (name "Net-(LED4-C)") (class "Default")
      (node (ref "LED4") (pin "K") (pinfunction "C_K") (pintype "passive"))
      (node (ref "R12") (pin "1") (pinfunction "1_1") (pintype "passive"))
    )
    (net (code "39") (name "Net-(LED5-C)") (class "Default")
      (node (ref "LED5") (pin "K") (pinfunction "C_K") (pintype "passive"))
      (node (ref "R15") (pin "1") (pinfunction "1_1") (pintype "passive"))
    )
    (net (code "40") (name "Net-(LED6-C)") (class "Default")
      (node (ref "LED6") (pin "K") (pinfunction "C_K") (pintype "passive"))
      (node (ref "R18") (pin "1") (pinfunction "1_1") (pintype "passive"))
    )
    (net (code "41") (name "Net-(LED7-C)") (class "Default")
      (node (ref "LED7") (pin "K") (pinfunction "C_K") (pintype "passive"))
      (node (ref "R21") (pin "1") (pinfunction "1_1") (pintype "passive"))
    )
    (net (code "42") (name "Net-(LED8-C)") (class "Default")
      (node (ref "LED8") (pin "K") (pinfunction "C_K") (pintype "passive"))
      (node (ref "R24") (pin "1") (pinfunction "1_1") (pintype "passive"))
    )
    (net (code "43") (name "Net-(LOAD1A-KL)") (class "Default")
      (node (ref "C3") (pin "2") (pinfunction "2_2") (pintype "passive"))
      (node (ref "LOAD1") (pin "1") (pinfunction "KL_1") (pintype "passive"))
      (node (ref "T1") (pin "T1") (pinfunction "A1_T1") (pintype "passive"))
    )
    (net (code "44") (name "Net-(LOAD2A-KL)") (class "Default")
      (node (ref "C10") (pin "2") (pinfunction "2_2") (pintype "passive"))
      (node (ref "LOAD2") (pin "1") (pinfunction "KL_1") (pintype "passive"))
      (node (ref "T2") (pin "T1") (pinfunction "A1_T1") (pintype "passive"))
    )
    (net (code "45") (name "Net-(LOAD3A-KL)") (class "Default")
      (node (ref "C11") (pin "2") (pinfunction "2_2") (pintype "passive"))
      (node (ref "LOAD3") (pin "1") (pinfunction "KL_1") (pintype "passive"))
      (node (ref "T3") (pin "T1") (pinfunction "A1_T1") (pintype "passive"))
    )
    (net (code "46") (name "Net-(LOAD4A-KL)") (class "Default")
      (node (ref "C12") (pin "2") (pinfunction "2_2") (pintype "passive"))
      (node (ref "LOAD4") (pin "1") (pinfunction "KL_1") (pintype "passive"))
      (node (ref "T4") (pin "T1") (pinfunction "A1_T1") (pintype "passive"))
    )
    (net (code "47") (name "Net-(LOAD5A-KL)") (class "Default")
      (node (ref "C13") (pin "2") (pinfunction "2_2") (pintype "passive"))
      (node (ref "LOAD5") (pin "1") (pinfunction "KL_1") (pintype "passive"))
      (node (ref "T5") (pin "T1") (pinfunction "A1_T1") (pintype "passive"))
    )
    (net (code "48") (name "Net-(LOAD6A-KL)") (class "Default")
      (node (ref "C14") (pin "2") (pinfunction "2_2") (pintype "passive"))
      (node (ref "LOAD6") (pin "1") (pinfunction "KL_1") (pintype "passive"))
      (node (ref "T6") (pin "T1") (pinfunction "A1_T1") (pintype "passive"))
    )
    (net (code "49") (name "Net-(LOAD7A-KL)") (class "Default")
      (node (ref "C15") (pin "2") (pinfunction "2_2") (pintype "passive"))
      (node (ref "LOAD7") (pin "1") (pinfunction "KL_1") (pintype "passive"))
      (node (ref "T7") (pin "T1") (pinfunction "A1_T1") (pintype "passive"))
    )
    (net (code "50") (name "Net-(LOAD8A-KL)") (class "Default")
      (node (ref "C16") (pin "2") (pinfunction "2_2") (pintype "passive"))
      (node (ref "LOAD8") (pin "1") (pinfunction "KL_1") (pintype "passive"))
      (node (ref "T8") (pin "T1") (pinfunction "A1_T1") (pintype "passive"))
    )
    (net (code "51") (name "Net-(OK1-A)") (class "Default")
      (node (ref "OK1") (pin "1") (pinfunction "A_1") (pintype "passive"))
      (node (ref "R1") (pin "2") (pinfunction "2_2") (pintype "passive"))
    )
    (net (code "52") (name "Net-(OK1-A1)") (class "Default")
      (node (ref "OK1") (pin "4") (pinfunction "A1_4") (pintype "passive"))
      (node (ref "T1") (pin "G") (pinfunction "G_G") (pintype "passive"))
    )
    (net (code "53") (name "Net-(OK1-A2)") (class "Default")
      (node (ref "OK1") (pin "6") (pinfunction "A2_6") (pintype "passive"))
      (node (ref "R2") (pin "1") (pinfunction "1_1") (pintype "passive"))
    )
    (net (code "54") (name "Net-(OK2-A)") (class "Default")
      (node (ref "OK2") (pin "1") (pinfunction "A_1") (pintype "passive"))
      (node (ref "R6") (pin "2") (pinfunction "2_2") (pintype "passive"))
    )
    (net (code "55") (name "Net-(OK2-A1)") (class "Default")
      (node (ref "OK2") (pin "4") (pinfunction "A1_4") (pintype "passive"))
      (node (ref "T2") (pin "G") (pinfunction "G_G") (pintype "passive"))
    )
    (net (code "56") (name "Net-(OK2-A2)") (class "Default")
      (node (ref "OK2") (pin "6") (pinfunction "A2_6") (pintype "passive"))
      (node (ref "R7") (pin "1") (pinfunction "1_1") (pintype "passive"))
    )
    (net (code "57") (name "Net-(OK3-A)") (class "Default")
      (node (ref "OK3") (pin "1") (pinfunction "A_1") (pintype "passive"))
      (node (ref "R9") (pin "2") (pinfunction "2_2") (pintype "passive"))
    )
    (net (code "58") (name "Net-(OK3-A1)") (class "Default")
      (node (ref "OK3") (pin "4") (pinfunction "A1_4") (pintype "passive"))
      (node (ref "T3") (pin "G") (pinfunction "G_G") (pintype "passive"))
    )
    (net (code "59") (name "Net-(OK3-A2)") (class "Default")
      (node (ref "OK3") (pin "6") (pinfunction "A2_6") (pintype "passive"))
      (node (ref "R10") (pin "1") (pinfunction "1_1") (pintype "passive"))
    )
    (net (code "60") (name "Net-(OK4-A)") (class "Default")
      (node (ref "OK4") (pin "1") (pinfunction "A_1") (pintype "passive"))
      (node (ref "R12") (pin "2") (pinfunction "2_2") (pintype "passive"))
    )
    (net (code "61") (name "Net-(OK4-A1)") (class "Default")
      (node (ref "OK4") (pin "4") (pinfunction "A1_4") (pintype "passive"))
      (node (ref "T4") (pin "G") (pinfunction "G_G") (pintype "passive"))
    )
    (net (code "62") (name "Net-(OK4-A2)") (class "Default")
      (node (ref "OK4") (pin "6") (pinfunction "A2_6") (pintype "passive"))
      (node (ref "R13") (pin "1") (pinfunction "1_1") (pintype "passive"))
    )
    (net (code "63") (name "Net-(OK5-A)") (class "Default")
      (node (ref "OK5") (pin "1") (pinfunction "A_1") (pintype "passive"))
      (node (ref "R15") (pin "2") (pinfunction "2_2") (pintype "passive"))
    )
    (net (code "64") (name "Net-(OK5-A1)") (class "Default")
      (node (ref "OK5") (pin "4") (pinfunction "A1_4") (pintype "passive"))
      (node (ref "T5") (pin "G") (pinfunction "G_G") (pintype "passive"))
    )
    (net (code "65") (name "Net-(OK5-A2)") (class "Default")
      (node (ref "OK5") (pin "6") (pinfunction "A2_6") (pintype "passive"))
      (node (ref "R16") (pin "1") (pinfunction "1_1") (pintype "passive"))
    )
    (net (code "66") (name "Net-(OK6-A)") (class "Default")
      (node (ref "OK6") (pin "1") (pinfunction "A_1") (pintype "passive"))
      (node (ref "R18") (pin "2") (pinfunction "2_2") (pintype "passive"))
    )
    (net (code "67") (name "Net-(OK6-A1)") (class "Default")
      (node (ref "OK6") (pin "4") (pinfunction "A1_4") (pintype "passive"))
      (node (ref "T6") (pin "G") (pinfunction "G_G") (pintype "passive"))
    )
    (net (code "68") (name "Net-(OK6-A2)") (class "Default")
      (node (ref "OK6") (pin "6") (pinfunction "A2_6") (pintype "passive"))
      (node (ref "R19") (pin "1") (pinfunction "1_1") (pintype "passive"))
    )
    (net (code "69") (name "Net-(OK7-A)") (class "Default")
      (node (ref "OK7") (pin "1") (pinfunction "A_1") (pintype "passive"))
      (node (ref "R21") (pin "2") (pinfunction "2_2") (pintype "passive"))
    )
    (net (code "70") (name "Net-(OK7-A1)") (class "Default")
      (node (ref "OK7") (pin "4") (pinfunction "A1_4") (pintype "passive"))
      (node (ref "T7") (pin "G") (pinfunction "G_G") (pintype "passive"))
    )
    (net (code "71") (name "Net-(OK7-A2)") (class "Default")
      (node (ref "OK7") (pin "6") (pinfunction "A2_6") (pintype "passive"))
      (node (ref "R22") (pin "1") (pinfunction "1_1") (pintype "passive"))
    )
    (net (code "72") (name "Net-(OK8-A)") (class "Default")
      (node (ref "OK8") (pin "1") (pinfunction "A_1") (pintype "passive"))
      (node (ref "R24") (pin "2") (pinfunction "2_2") (pintype "passive"))
    )
    (net (code "73") (name "Net-(OK8-A1)") (class "Default")
      (node (ref "OK8") (pin "4") (pinfunction "A1_4") (pintype "passive"))
      (node (ref "T8") (pin "G") (pinfunction "G_G") (pintype "passive"))
    )
    (net (code "74") (name "Net-(OK8-A2)") (class "Default")
      (node (ref "OK8") (pin "6") (pinfunction "A2_6") (pintype "passive"))
      (node (ref "R25") (pin "1") (pinfunction "1_1") (pintype "passive"))
    )
    (net (code "75") (name "Net-(R30-Pad2)") (class "Default")
      (node (ref "R30") (pin "2") (pinfunction "2_2") (pintype "passive"))
      (node (ref "T9") (pin "B") (pinfunction "B_B") (pintype "passive"))
    )
    (net (code "76") (name "unconnected-(CUR_SENS_JACK-LEFT-PadTIP)") (class "Default")
      (node (ref "CUR_SENS_JACK") (pin "TIP") (pinfunction "LEFT_TIP") (pintype "bidirectional"))
    )
    (net (code "77") (name "unconnected-(D1-C5-Pad6)") (class "Default")
      (node (ref "D1") (pin "6") (pinfunction "C5_6") (pintype "passive"))
    )
    (net (code "78") (name "unconnected-(J1-VPP-PadC6)") (class "Default")
      (node (ref "J1") (pin "C6") (pinfunction "VPP_C6") (pintype "input"))
    )
    (net (code "79") (name "unconnected-(SIM900TECAA-B-Pad33)") (class "Default")
      (node (ref "SIM900TEC") (pin "33") (pinfunction "B_33") (pintype "passive"))
    )
    (net (code "80") (name "unconnected-(SIM900TECAB-B-Pad34)") (class "Default")
      (node (ref "SIM900TEC") (pin "34") (pinfunction "B_34") (pintype "passive"))
    )
    (net (code "81") (name "unconnected-(SIM900TECAC-B-Pad35)") (class "Default")
      (node (ref "SIM900TEC") (pin "35") (pinfunction "B_35") (pintype "passive"))
    )
    (net (code "82") (name "unconnected-(SIM900TECAD-B-Pad36)") (class "Default")
      (node (ref "SIM900TEC") (pin "36") (pinfunction "B_36") (pintype "passive"))
    )
    (net (code "83") (name "unconnected-(SIM900TECAE-B-Pad37)") (class "Default")
      (node (ref "SIM900TEC") (pin "37") (pinfunction "B_37") (pintype "passive"))
    )
    (net (code "84") (name "unconnected-(SIM900TECAF-B-Pad38)") (class "Default")
      (node (ref "SIM900TEC") (pin "38") (pinfunction "B_38") (pintype "passive"))
    )
    (net (code "85") (name "unconnected-(SIM900TECAG-B-Pad39)") (class "Default")
      (node (ref "SIM900TEC") (pin "39") (pinfunction "B_39") (pintype "passive"))
    )
    (net (code "86") (name "unconnected-(SIM900TECAI-B-Pad40)") (class "Default")
      (node (ref "SIM900TEC") (pin "40") (pinfunction "B_40") (pintype "passive"))
    )
    (net (code "87") (name "unconnected-(SIM900TECAK-B-Pad42)") (class "Default")
      (node (ref "SIM900TEC") (pin "42") (pinfunction "B_42") (pintype "passive"))
    )
    (net (code "88") (name "unconnected-(SIM900TECAM-B-Pad44)") (class "Default")
      (node (ref "SIM900TEC") (pin "44") (pinfunction "B_44") (pintype "passive"))
    )
    (net (code "89") (name "unconnected-(SIM900TECAN-B-Pad45)") (class "Default")
      (node (ref "SIM900TEC") (pin "45") (pinfunction "B_45") (pintype "passive"))
    )
    (net (code "90") (name "unconnected-(SIM900TECAO-B-Pad46)") (class "Default")
      (node (ref "SIM900TEC") (pin "46") (pinfunction "B_46") (pintype "passive"))
    )
    (net (code "91") (name "unconnected-(SIM900TECAP-B-Pad47)") (class "Default")
      (node (ref "SIM900TEC") (pin "47") (pinfunction "B_47") (pintype "passive"))
    )
    (net (code "92") (name "unconnected-(SIM900TECAQ-B-Pad48)") (class "Default")
      (node (ref "SIM900TEC") (pin "48") (pinfunction "B_48") (pintype "passive"))
    )
    (net (code "93") (name "unconnected-(SIM900TECAR-B-Pad49)") (class "Default")
      (node (ref "SIM900TEC") (pin "49") (pinfunction "B_49") (pintype "passive"))
    )
    (net (code "94") (name "unconnected-(SIM900TECAT-B-Pad50)") (class "Default")
      (node (ref "SIM900TEC") (pin "50") (pinfunction "B_50") (pintype "passive"))
    )
    (net (code "95") (name "unconnected-(SIM900TECAW-B-Pad53)") (class "Default")
      (node (ref "SIM900TEC") (pin "53") (pinfunction "B_53") (pintype "passive"))
    )
    (net (code "96") (name "unconnected-(SIM900TECAX-B-Pad54)") (class "Default")
      (node (ref "SIM900TEC") (pin "54") (pinfunction "B_54") (pintype "passive"))
    )
    (net (code "97") (name "unconnected-(SIM900TECAY-B-Pad55)") (class "Default")
      (node (ref "SIM900TEC") (pin "55") (pinfunction "B_55") (pintype "passive"))
    )
    (net (code "98") (name "unconnected-(SIM900TECAZ-B-Pad56)") (class "Default")
      (node (ref "SIM900TEC") (pin "56") (pinfunction "B_56") (pintype "passive"))
    )
    (net (code "99") (name "unconnected-(SIM900TECBA-B-Pad57)") (class "Default")
      (node (ref "SIM900TEC") (pin "57") (pinfunction "B_57") (pintype "passive"))
    )
    (net (code "100") (name "unconnected-(SIM900TECBB-B-Pad58)") (class "Default")
      (node (ref "SIM900TEC") (pin "58") (pinfunction "B_58") (pintype "passive"))
    )
    (net (code "101") (name "unconnected-(SIM900TECBC-B-Pad59)") (class "Default")
      (node (ref "SIM900TEC") (pin "59") (pinfunction "B_59") (pintype "passive"))
    )
    (net (code "102") (name "unconnected-(SIM900TECBE-B-Pad60)") (class "Default")
      (node (ref "SIM900TEC") (pin "60") (pinfunction "B_60") (pintype "passive"))
    )
    (net (code "103") (name "unconnected-(SIM900TECC-B-Pad11)") (class "Default")
      (node (ref "SIM900TEC") (pin "11") (pinfunction "B_11") (pintype "passive"))
    )
    (net (code "104") (name "unconnected-(SIM900TECD-B-Pad12)") (class "Default")
      (node (ref "SIM900TEC") (pin "12") (pinfunction "B_12") (pintype "passive"))
    )
    (net (code "105") (name "unconnected-(SIM900TECE-B-Pad13)") (class "Default")
      (node (ref "SIM900TEC") (pin "13") (pinfunction "B_13") (pintype "passive"))
    )
    (net (code "106") (name "unconnected-(SIM900TECF-B-Pad14)") (class "Default")
      (node (ref "SIM900TEC") (pin "14") (pinfunction "B_14") (pintype "passive"))
    )
    (net (code "107") (name "unconnected-(SIM900TECG-B-Pad15)") (class "Default")
      (node (ref "SIM900TEC") (pin "15") (pinfunction "B_15") (pintype "passive"))
    )
    (net (code "108") (name "unconnected-(SIM900TECH-B-Pad16)") (class "Default")
      (node (ref "SIM900TEC") (pin "16") (pinfunction "B_16") (pintype "passive"))
    )
    (net (code "109") (name "unconnected-(SIM900TECJ-B-Pad18)") (class "Default")
      (node (ref "SIM900TEC") (pin "18") (pinfunction "B_18") (pintype "passive"))
    )
    (net (code "110") (name "unconnected-(SIM900TECK-B-Pad19)") (class "Default")
      (node (ref "SIM900TEC") (pin "19") (pinfunction "B_19") (pintype "passive"))
    )
    (net (code "111") (name "unconnected-(SIM900TECM-B-Pad20)") (class "Default")
      (node (ref "SIM900TEC") (pin "20") (pinfunction "B_20") (pintype "passive"))
    )
    (net (code "112") (name "unconnected-(SIM900TECN-B-Pad21)") (class "Default")
      (node (ref "SIM900TEC") (pin "21") (pinfunction "B_21") (pintype "passive"))
    )
    (net (code "113") (name "unconnected-(SIM900TECO-B-Pad22)") (class "Default")
      (node (ref "SIM900TEC") (pin "22") (pinfunction "B_22") (pintype "passive"))
    )
    (net (code "114") (name "unconnected-(SIM900TECP-B-Pad23)") (class "Default")
      (node (ref "SIM900TEC") (pin "23") (pinfunction "B_23") (pintype "passive"))
    )
    (net (code "115") (name "unconnected-(SIM900TECQ-B-Pad24)") (class "Default")
      (node (ref "SIM900TEC") (pin "24") (pinfunction "B_24") (pintype "passive"))
    )
    (net (code "116") (name "unconnected-(SIM900TECS-B-Pad26)") (class "Default")
      (node (ref "SIM900TEC") (pin "26") (pinfunction "B_26") (pintype "passive"))
    )
    (net (code "117") (name "unconnected-(SIM900TECU-B-Pad28)") (class "Default")
      (node (ref "SIM900TEC") (pin "28") (pinfunction "B_28") (pintype "passive"))
    )
    (net (code "118") (name "unconnected-(SIM900TECX-B-Pad30)") (class "Default")
      (node (ref "SIM900TEC") (pin "30") (pinfunction "B_30") (pintype "passive"))
    )
    (net (code "119") (name "unconnected-(SIM900TECZ-B-Pad32)") (class "Default")
      (node (ref "SIM900TEC") (pin "32") (pinfunction "B_32") (pintype "passive"))
    )
    (net (code "120") (name "unconnected-(U$1-*10-Pad13)") (class "Default")
      (node (ref "U$1") (pin "13") (pinfunction "*10_13") (pintype "bidirectional"))
    )
    (net (code "121") (name "unconnected-(U$1-*11-Pad14)") (class "Default")
      (node (ref "U$1") (pin "14") (pinfunction "*11_14") (pintype "bidirectional"))
    )
    (net (code "122") (name "unconnected-(U$1-12-Pad15)") (class "Default")
      (node (ref "U$1") (pin "15") (pinfunction "12_15") (pintype "bidirectional"))
    )
    (net (code "123") (name "unconnected-(U$1-13-Pad16)") (class "Default")
      (node (ref "U$1") (pin "16") (pinfunction "13_16") (pintype "bidirectional"))
    )
    (net (code "124") (name "unconnected-(U$1-A0-Pad17)") (class "Default")
      (node (ref "U$1") (pin "17") (pinfunction "A0_17") (pintype "bidirectional"))
    )
    (net (code "125") (name "unconnected-(U$1-A1-Pad18)") (class "Default")
      (node (ref "U$1") (pin "18") (pinfunction "A1_18") (pintype "bidirectional"))
    )
    (net (code "126") (name "unconnected-(U$1-RAW-Pad24)") (class "Default")
      (node (ref "U$1") (pin "24") (pinfunction "RAW_24") (pintype "bidirectional"))
    )
    (net (code "127") (name "unconnected-(U$1-RST-Pad3)") (class "Default")
      (node (ref "U$1") (pin "3") (pinfunction "RST_3") (pintype "bidirectional"))
    )
    (net (code "128") (name "unconnected-(U$1-RST-Pad22)") (class "Default")
      (node (ref "U$1") (pin "22") (pinfunction "RST_22") (pintype "bidirectional"))
    )
  )
)
